# hat.net
KiCad netlist of a schematic drawn in EasyEDA
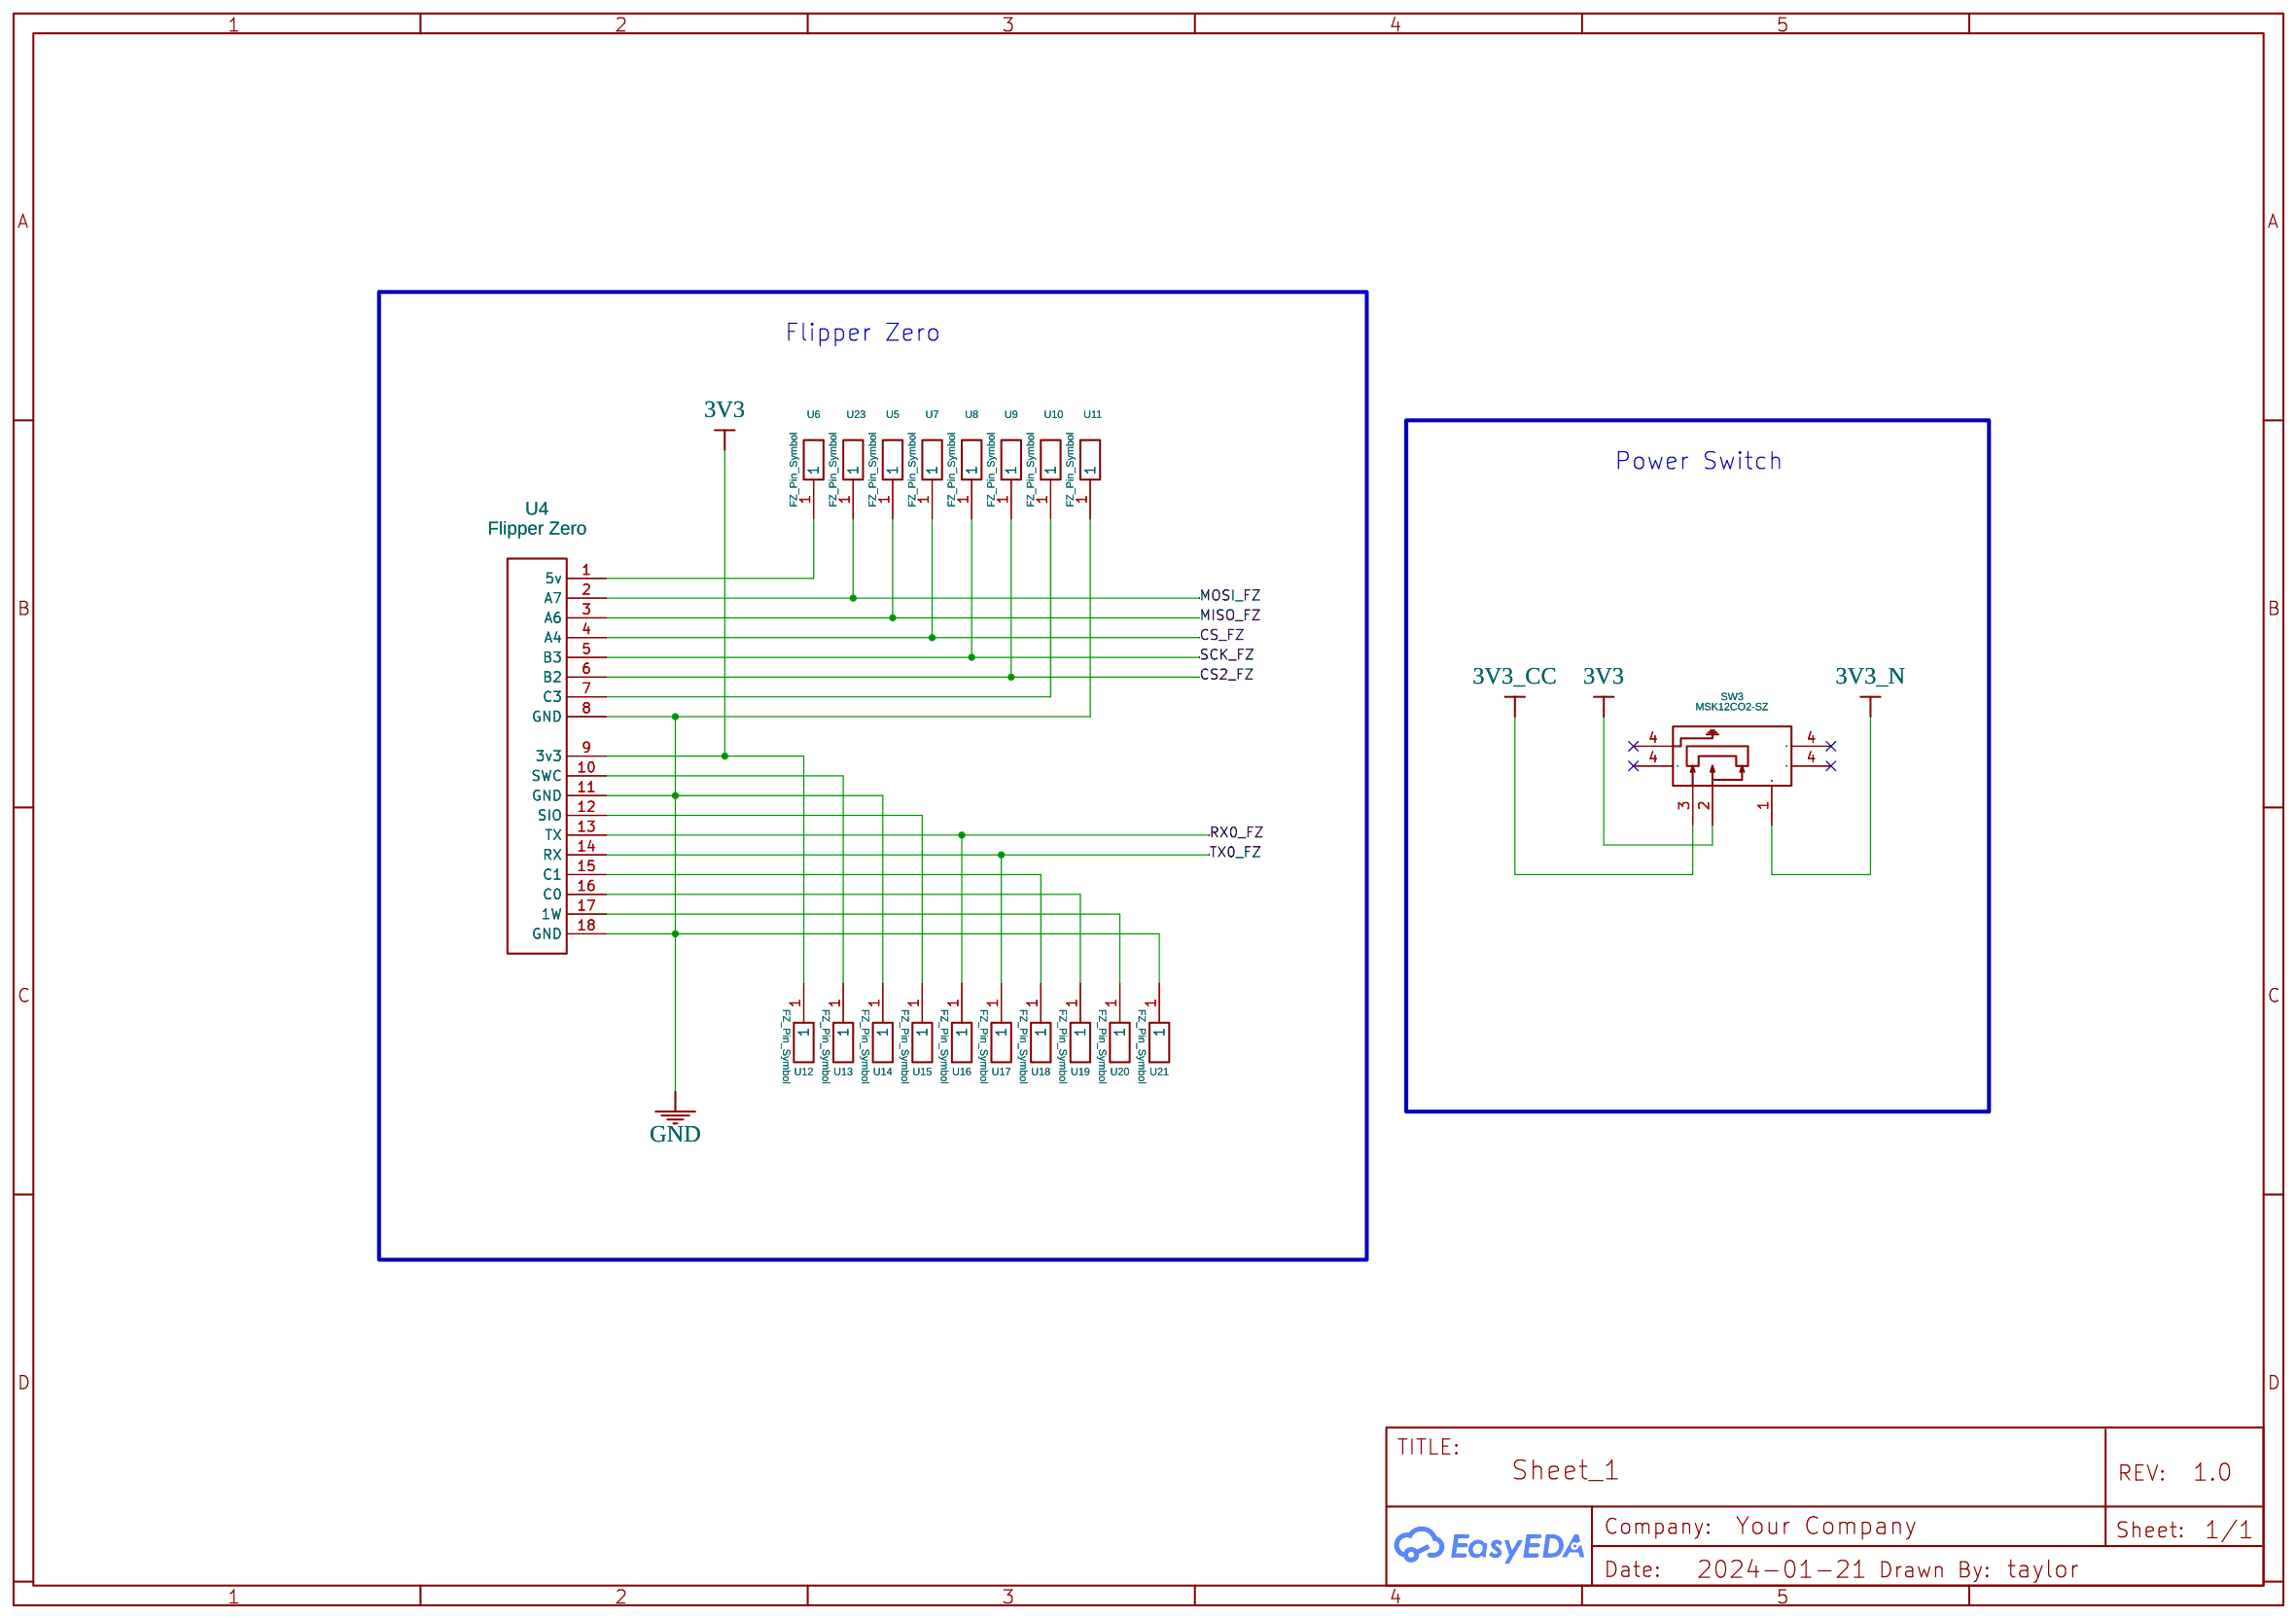
[diagram p0: Sheet_1]
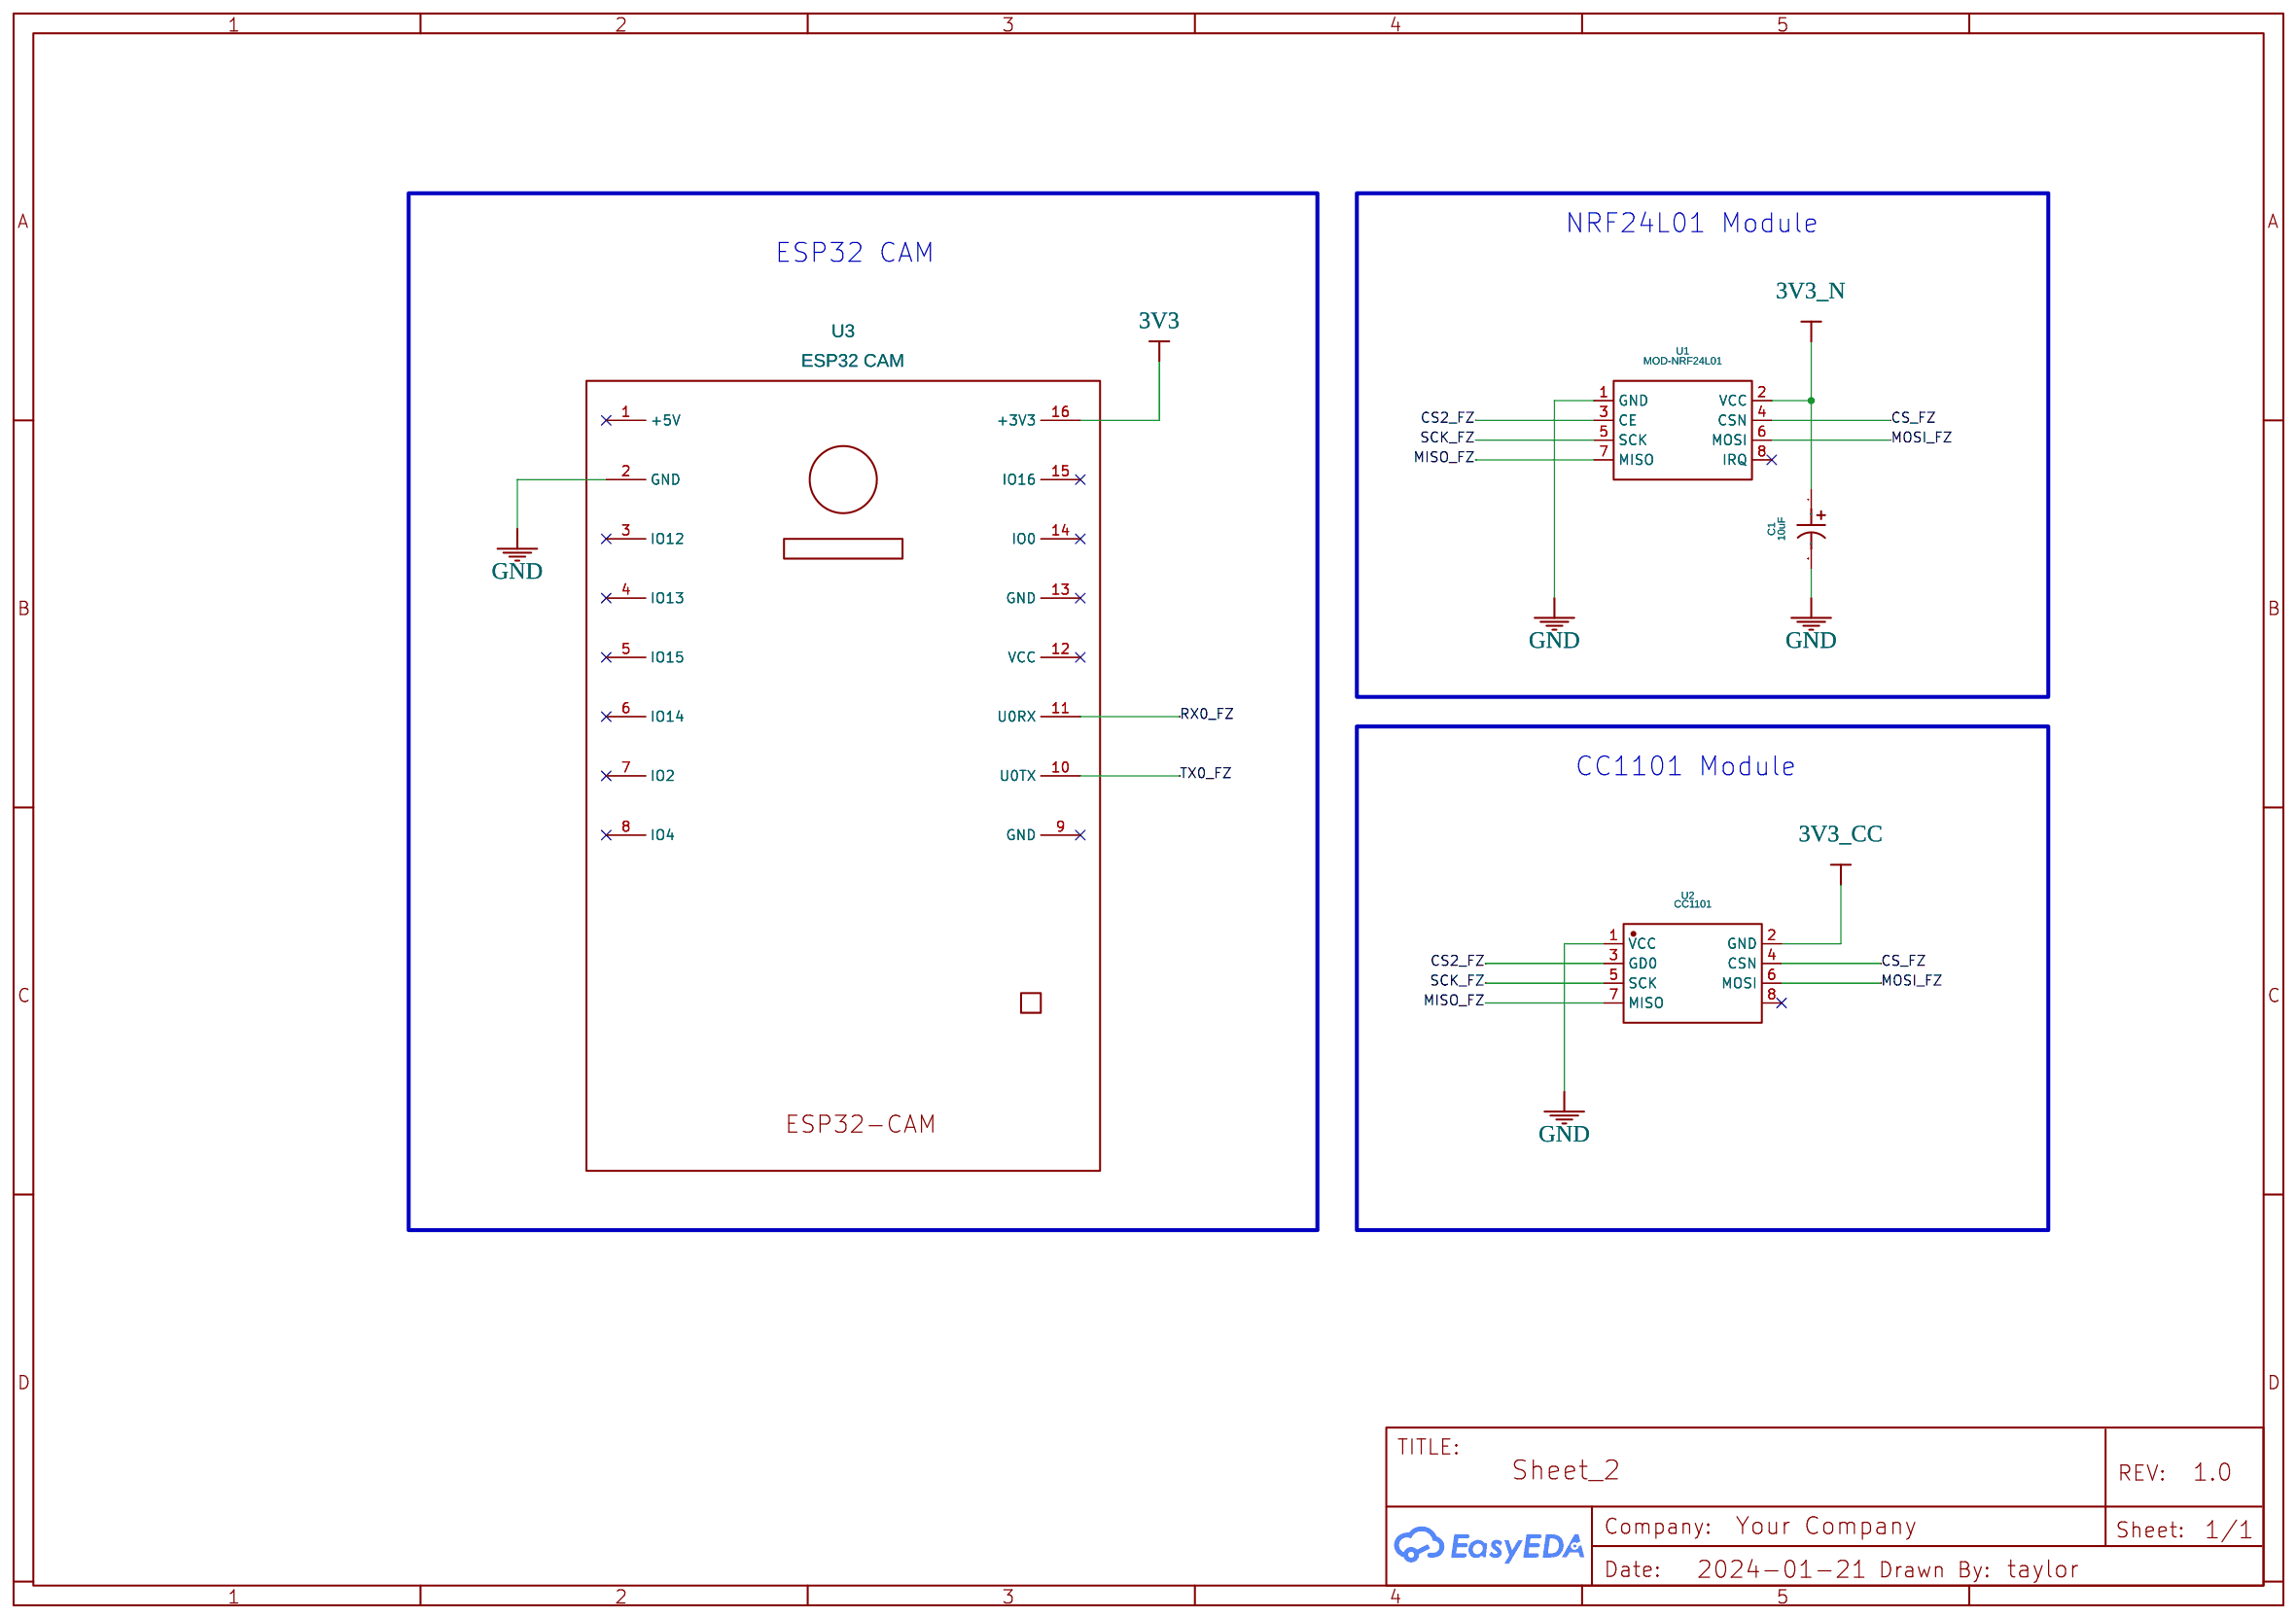
[diagram p1: Sheet_2]

(export (version "E")
  (design (tool "Eeschema 10.0.6"))
  (components
    (comp (ref "SW3")
      (value "MSK12CO2-SZ")
      (fields (field (name "Manufacturer") "SHOU HAN(首韩)"))
      (libsource (lib "") (part "MSK12CO2-SZ"))
    )
    (comp (ref "U4") (value "Flipper Zero") (libsource (lib "") (part "Flipper Zero")))
    (comp (ref "U5") (value "FZ_Pin_Symbol") (libsource (lib "") (part "FZ_Pin_Symbol")))
    (comp (ref "U6") (value "FZ_Pin_Symbol") (libsource (lib "") (part "FZ_Pin_Symbol")))
    (comp (ref "U7") (value "FZ_Pin_Symbol") (libsource (lib "") (part "FZ_Pin_Symbol")))
    (comp (ref "U8") (value "FZ_Pin_Symbol") (libsource (lib "") (part "FZ_Pin_Symbol")))
    (comp (ref "U9") (value "FZ_Pin_Symbol") (libsource (lib "") (part "FZ_Pin_Symbol")))
    (comp (ref "U10") (value "FZ_Pin_Symbol") (libsource (lib "") (part "FZ_Pin_Symbol")))
    (comp (ref "U11") (value "FZ_Pin_Symbol") (libsource (lib "") (part "FZ_Pin_Symbol")))
    (comp (ref "U12") (value "FZ_Pin_Symbol") (libsource (lib "") (part "FZ_Pin_Symbol_1")))
    (comp (ref "U13") (value "FZ_Pin_Symbol") (libsource (lib "") (part "FZ_Pin_Symbol_1")))
    (comp (ref "U14") (value "FZ_Pin_Symbol") (libsource (lib "") (part "FZ_Pin_Symbol_1")))
    (comp (ref "U15") (value "FZ_Pin_Symbol") (libsource (lib "") (part "FZ_Pin_Symbol_1")))
    (comp (ref "U16") (value "FZ_Pin_Symbol") (libsource (lib "") (part "FZ_Pin_Symbol_1")))
    (comp (ref "U17") (value "FZ_Pin_Symbol") (libsource (lib "") (part "FZ_Pin_Symbol_1")))
    (comp (ref "U18") (value "FZ_Pin_Symbol") (libsource (lib "") (part "FZ_Pin_Symbol_1")))
    (comp (ref "U19") (value "FZ_Pin_Symbol") (libsource (lib "") (part "FZ_Pin_Symbol_1")))
    (comp (ref "U20") (value "FZ_Pin_Symbol") (libsource (lib "") (part "FZ_Pin_Symbol_1")))
    (comp (ref "U21") (value "FZ_Pin_Symbol") (libsource (lib "") (part "FZ_Pin_Symbol_1")))
    (comp (ref "U23") (value "FZ_Pin_Symbol") (libsource (lib "") (part "FZ_Pin_Symbol")))
    (comp (ref "C1")
      (value "10uF")
      (fields (field (name "Manufacturer Part") "RST10UF50V016") (field (name "Manufacturer") "KNSCHA(科尼盛)"))
      (libsource (lib "") (part "RST10UF50V016"))
    )
    (comp (ref "U1") (value "MOD-NRF24L01") (libsource (lib "") (part "MOD-NRF24L01")))
    (comp (ref "U2") (value "CC1101") (libsource (lib "") (part "CC1101")))
    (comp (ref "U3") (value "ESP32 CAM") (libsource (lib "") (part "ESP32 CAM")))
  )
  (nets
    (net (code "1") (name "3V3") (class "Default")
      (node (ref "SW3") (pin "2") (pinfunction "2_2") (pintype "unspecified"))
      (node (ref "U12") (pin "1") (pinfunction "1_1") (pintype "unspecified"))
      (node (ref "U3") (pin "16") (pinfunction "+3V3_16") (pintype "unspecified"))
      (node (ref "U4") (pin "9") (pinfunction "3v3_9") (pintype "unspecified"))
    )
    (net (code "2") (name "3V3_CC") (class "Default")
      (node (ref "SW3") (pin "3") (pinfunction "3_3") (pintype "unspecified"))
      (node (ref "U2") (pin "2") (pinfunction "GND_2") (pintype "unspecified"))
    )
    (net (code "3") (name "3V3_N") (class "Default")
      (node (ref "C1") (pin "1") (pinfunction "1_1") (pintype "input"))
      (node (ref "SW3") (pin "1") (pinfunction "1_1") (pintype "unspecified"))
      (node (ref "U1") (pin "2") (pinfunction "VCC_2") (pintype "unspecified"))
    )
    (net (code "4") (name "CS2_FZ") (class "Default")
      (node (ref "U1") (pin "3") (pinfunction "CE_3") (pintype "unspecified"))
      (node (ref "U2") (pin "3") (pinfunction "GD0_3") (pintype "unspecified"))
      (node (ref "U4") (pin "6") (pinfunction "B2_6") (pintype "unspecified"))
      (node (ref "U9") (pin "1") (pinfunction "1_1") (pintype "unspecified"))
    )
    (net (code "5") (name "CS_FZ") (class "Default")
      (node (ref "U1") (pin "4") (pinfunction "CSN_4") (pintype "unspecified"))
      (node (ref "U2") (pin "4") (pinfunction "CSN_4") (pintype "unspecified"))
      (node (ref "U4") (pin "4") (pinfunction "A4_4") (pintype "unspecified"))
      (node (ref "U7") (pin "1") (pinfunction "1_1") (pintype "unspecified"))
    )
    (net (code "6") (name "GND") (class "Default")
      (node (ref "C1") (pin "2") (pinfunction "2_2") (pintype "input"))
      (node (ref "U1") (pin "1") (pinfunction "GND_1") (pintype "unspecified"))
      (node (ref "U11") (pin "1") (pinfunction "1_1") (pintype "unspecified"))
      (node (ref "U14") (pin "1") (pinfunction "1_1") (pintype "unspecified"))
      (node (ref "U2") (pin "1") (pinfunction "VCC_1") (pintype "unspecified"))
      (node (ref "U21") (pin "1") (pinfunction "1_1") (pintype "unspecified"))
      (node (ref "U3") (pin "2") (pinfunction "GND_2") (pintype "unspecified"))
      (node (ref "U4") (pin "11") (pinfunction "GND_11") (pintype "unspecified"))
      (node (ref "U4") (pin "18") (pinfunction "GND_18") (pintype "unspecified"))
      (node (ref "U4") (pin "8") (pinfunction "GND_8") (pintype "unspecified"))
    )
    (net (code "7") (name "MISO_FZ") (class "Default")
      (node (ref "U1") (pin "7") (pinfunction "MISO_7") (pintype "unspecified"))
      (node (ref "U2") (pin "7") (pinfunction "MISO_7") (pintype "unspecified"))
      (node (ref "U4") (pin "3") (pinfunction "A6_3") (pintype "unspecified"))
      (node (ref "U5") (pin "1") (pinfunction "1_1") (pintype "unspecified"))
    )
    (net (code "8") (name "MOSI_FZ") (class "Default")
      (node (ref "U1") (pin "6") (pinfunction "MOSI_6") (pintype "unspecified"))
      (node (ref "U2") (pin "6") (pinfunction "MOSI_6") (pintype "unspecified"))
      (node (ref "U23") (pin "1") (pinfunction "1_1") (pintype "unspecified"))
      (node (ref "U4") (pin "2") (pinfunction "A7_2") (pintype "unspecified"))
    )
    (net (code "9") (name "Net-(U4-1W)") (class "Default")
      (node (ref "U20") (pin "1") (pinfunction "1_1") (pintype "unspecified"))
      (node (ref "U4") (pin "17") (pinfunction "1W_17") (pintype "unspecified"))
    )
    (net (code "10") (name "Net-(U4-5v)") (class "Default")
      (node (ref "U4") (pin "1") (pinfunction "5v_1") (pintype "unspecified"))
      (node (ref "U6") (pin "1") (pinfunction "1_1") (pintype "unspecified"))
    )
    (net (code "11") (name "Net-(U4-C0)") (class "Default")
      (node (ref "U19") (pin "1") (pinfunction "1_1") (pintype "unspecified"))
      (node (ref "U4") (pin "16") (pinfunction "C0_16") (pintype "unspecified"))
    )
    (net (code "12") (name "Net-(U4-C1)") (class "Default")
      (node (ref "U18") (pin "1") (pinfunction "1_1") (pintype "unspecified"))
      (node (ref "U4") (pin "15") (pinfunction "C1_15") (pintype "unspecified"))
    )
    (net (code "13") (name "Net-(U4-C3)") (class "Default")
      (node (ref "U10") (pin "1") (pinfunction "1_1") (pintype "unspecified"))
      (node (ref "U4") (pin "7") (pinfunction "C3_7") (pintype "unspecified"))
    )
    (net (code "14") (name "Net-(U4-SIO)") (class "Default")
      (node (ref "U15") (pin "1") (pinfunction "1_1") (pintype "unspecified"))
      (node (ref "U4") (pin "12") (pinfunction "SIO_12") (pintype "unspecified"))
    )
    (net (code "15") (name "Net-(U4-SWC)") (class "Default")
      (node (ref "U13") (pin "1") (pinfunction "1_1") (pintype "unspecified"))
      (node (ref "U4") (pin "10") (pinfunction "SWC_10") (pintype "unspecified"))
    )
    (net (code "16") (name "RX0_FZ") (class "Default")
      (node (ref "U16") (pin "1") (pinfunction "1_1") (pintype "unspecified"))
      (node (ref "U3") (pin "11") (pinfunction "U0RX_11") (pintype "unspecified"))
      (node (ref "U4") (pin "13") (pinfunction "TX_13") (pintype "unspecified"))
    )
    (net (code "17") (name "SCK_FZ") (class "Default")
      (node (ref "U1") (pin "5") (pinfunction "SCK_5") (pintype "unspecified"))
      (node (ref "U2") (pin "5") (pinfunction "SCK_5") (pintype "unspecified"))
      (node (ref "U4") (pin "5") (pinfunction "B3_5") (pintype "unspecified"))
      (node (ref "U8") (pin "1") (pinfunction "1_1") (pintype "unspecified"))
    )
    (net (code "18") (name "TX0_FZ") (class "Default")
      (node (ref "U17") (pin "1") (pinfunction "1_1") (pintype "unspecified"))
      (node (ref "U3") (pin "10") (pinfunction "U0TX_10") (pintype "unspecified"))
      (node (ref "U4") (pin "14") (pinfunction "RX_14") (pintype "unspecified"))
    )
    (net (code "19") (name "unconnected-(SW3-Pad4)") (class "Default")
      (node (ref "SW3") (pin "4") (pinfunction "4_4") (pintype "unspecified+no_connect"))
    )
    (net (code "20") (name "unconnected-(SW3-Pad4)_1") (class "Default")
      (node (ref "SW3") (pin "4") (pinfunction "4_4") (pintype "unspecified+no_connect"))
    )
    (net (code "21") (name "unconnected-(SW3-Pad4)_2") (class "Default")
      (node (ref "SW3") (pin "4") (pinfunction "4_4") (pintype "unspecified+no_connect"))
    )
    (net (code "22") (name "unconnected-(SW3-Pad4)_3") (class "Default")
      (node (ref "SW3") (pin "4") (pinfunction "4_4") (pintype "unspecified+no_connect"))
    )
    (net (code "23") (name "unconnected-(U1-IRQ-Pad8)") (class "Default")
      (node (ref "U1") (pin "8") (pinfunction "IRQ_8") (pintype "unspecified+no_connect"))
    )
    (net (code "24") (name "unconnected-(U2-Pad8)") (class "Default")
      (node (ref "U2") (pin "8") (pintype "unspecified+no_connect"))
    )
    (net (code "25") (name "unconnected-(U3-+5V-Pad1)") (class "Default")
      (node (ref "U3") (pin "1") (pinfunction "+5V_1") (pintype "unspecified+no_connect"))
    )
    (net (code "26") (name "unconnected-(U3-GND-Pad9)") (class "Default")
      (node (ref "U3") (pin "9") (pinfunction "GND_9") (pintype "unspecified+no_connect"))
    )
    (net (code "27") (name "unconnected-(U3-GND-Pad13)") (class "Default")
      (node (ref "U3") (pin "13") (pinfunction "GND_13") (pintype "unspecified+no_connect"))
    )
    (net (code "28") (name "unconnected-(U3-IO0-Pad14)") (class "Default")
      (node (ref "U3") (pin "14") (pinfunction "IO0_14") (pintype "unspecified+no_connect"))
    )
    (net (code "29") (name "unconnected-(U3-IO2-Pad7)") (class "Default")
      (node (ref "U3") (pin "7") (pinfunction "IO2_7") (pintype "unspecified+no_connect"))
    )
    (net (code "30") (name "unconnected-(U3-IO4-Pad8)") (class "Default")
      (node (ref "U3") (pin "8") (pinfunction "IO4_8") (pintype "unspecified+no_connect"))
    )
    (net (code "31") (name "unconnected-(U3-IO12-Pad3)") (class "Default")
      (node (ref "U3") (pin "3") (pinfunction "IO12_3") (pintype "unspecified+no_connect"))
    )
    (net (code "32") (name "unconnected-(U3-IO13-Pad4)") (class "Default")
      (node (ref "U3") (pin "4") (pinfunction "IO13_4") (pintype "unspecified+no_connect"))
    )
    (net (code "33") (name "unconnected-(U3-IO14-Pad6)") (class "Default")
      (node (ref "U3") (pin "6") (pinfunction "IO14_6") (pintype "unspecified+no_connect"))
    )
    (net (code "34") (name "unconnected-(U3-IO15-Pad5)") (class "Default")
      (node (ref "U3") (pin "5") (pinfunction "IO15_5") (pintype "unspecified+no_connect"))
    )
    (net (code "35") (name "unconnected-(U3-IO16-Pad15)") (class "Default")
      (node (ref "U3") (pin "15") (pinfunction "IO16_15") (pintype "unspecified+no_connect"))
    )
    (net (code "36") (name "unconnected-(U3-VCC-Pad12)") (class "Default")
      (node (ref "U3") (pin "12") (pinfunction "VCC_12") (pintype "unspecified+no_connect"))
    )
  )
)
